# relocker_schematic_cleaned.net
KiCad netlist of a schematic drawn in EAGLE
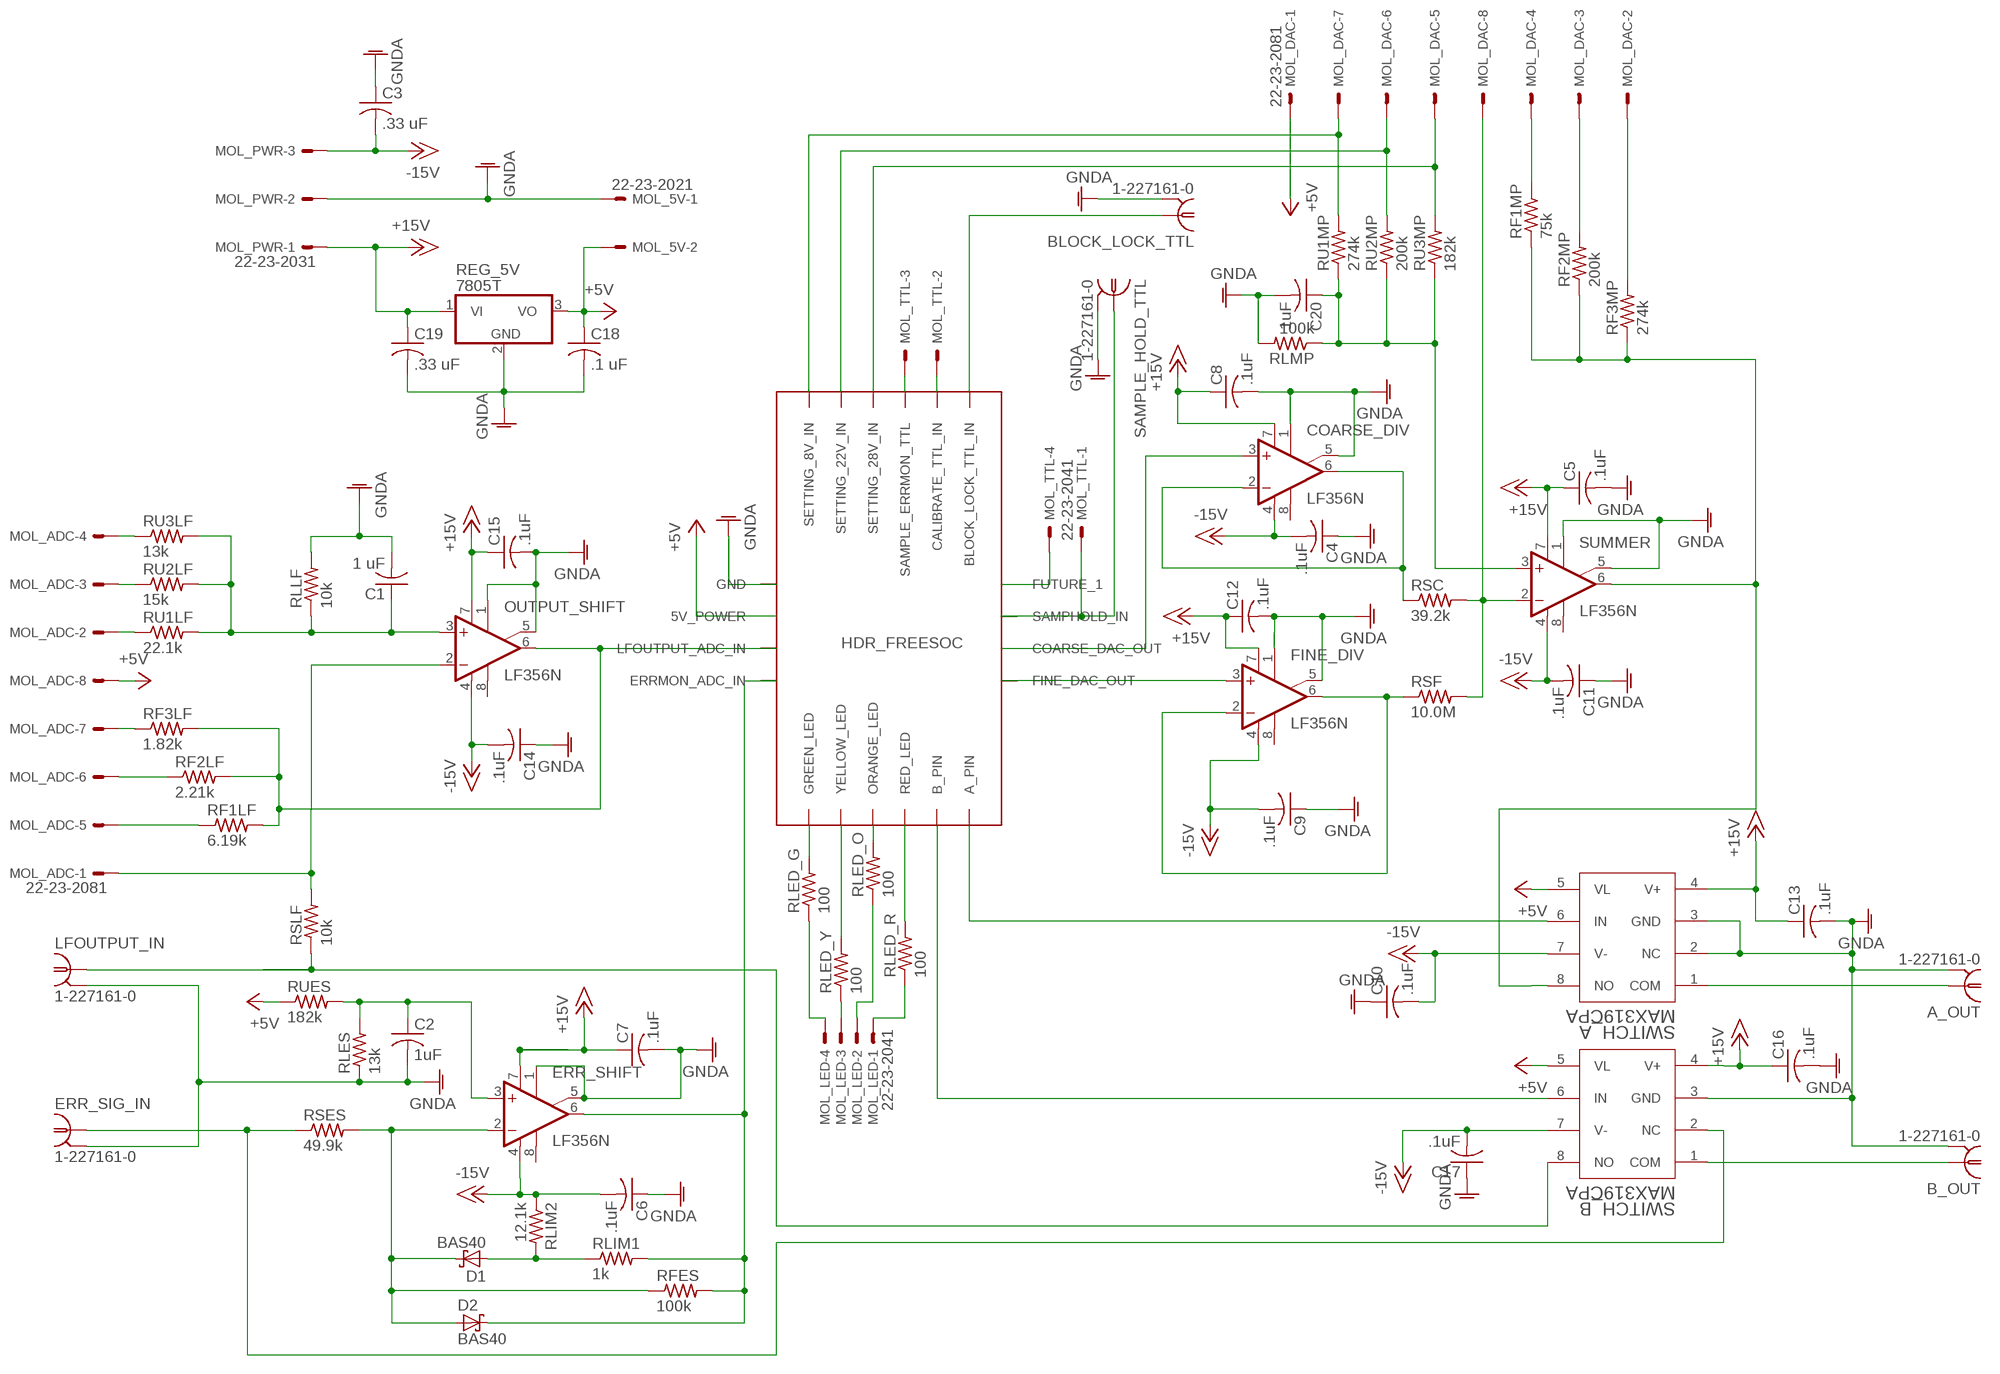
[diagram p0: schematic, sheet 1]

(export (version "E")
  (design (tool "Eeschema 10.0.6"))
  (components
    (comp (ref "A_OUT")
      (value "1-227161-0")
      (footprint "eagle-import:AMP_227161")
      (fields (field (name "MF") "TYCO ELECTRONICS") (field (name "MPN") "1-227161"))
      (libsource (lib "eagle-import") (part "?2271611--0"))
    )
    (comp (ref "BLOCK_LOCK_TTL")
      (value "1-227161-0")
      (footprint "eagle-import:AMP_227161")
      (fields (field (name "MF") "TYCO ELECTRONICS") (field (name "MPN") "1-227161"))
      (libsource (lib "eagle-import") (part "?2271611--0"))
    )
    (comp (ref "B_OUT")
      (value "1-227161-0")
      (footprint "eagle-import:AMP_227161")
      (fields (field (name "MF") "TYCO ELECTRONICS") (field (name "MPN") "1-227161"))
      (libsource (lib "eagle-import") (part "?2271611--0"))
    )
    (comp (ref "C1")
      (value "1 uF")
      (footprint "eagle-import:C0805")
      (libsource (lib "eagle-import") (part "C-USC0805"))
    )
    (comp (ref "C2")
      (value "1uF")
      (footprint "eagle-import:C0805")
      (libsource (lib "eagle-import") (part "C-USC0805"))
    )
    (comp (ref "C3")
      (value ".33 uF")
      (footprint "eagle-import:C0805")
      (libsource (lib "eagle-import") (part "C-USC0805"))
    )
    (comp (ref "C4")
      (value ".1uF")
      (footprint "eagle-import:C0805")
      (libsource (lib "eagle-import") (part "C-USC0805"))
    )
    (comp (ref "C5")
      (value ".1uF")
      (footprint "eagle-import:C0805")
      (libsource (lib "eagle-import") (part "C-USC0805"))
    )
    (comp (ref "C6")
      (value ".1uF")
      (footprint "eagle-import:C0805")
      (libsource (lib "eagle-import") (part "C-USC0805"))
    )
    (comp (ref "C7")
      (value ".1uF")
      (footprint "eagle-import:C0805")
      (libsource (lib "eagle-import") (part "C-USC0805"))
    )
    (comp (ref "C8")
      (value ".1uF")
      (footprint "eagle-import:C0805")
      (libsource (lib "eagle-import") (part "C-USC0805"))
    )
    (comp (ref "C9")
      (value ".1uF")
      (footprint "eagle-import:C0805")
      (libsource (lib "eagle-import") (part "C-USC0805"))
    )
    (comp (ref "C10")
      (value ".1uF")
      (footprint "eagle-import:C0805")
      (libsource (lib "eagle-import") (part "C-USC0805"))
    )
    (comp (ref "C11")
      (value ".1uF")
      (footprint "eagle-import:C0805")
      (libsource (lib "eagle-import") (part "C-USC0805"))
    )
    (comp (ref "C12")
      (value ".1uF")
      (footprint "eagle-import:C0805")
      (libsource (lib "eagle-import") (part "C-USC0805"))
    )
    (comp (ref "C13")
      (value ".1uF")
      (footprint "eagle-import:C0805")
      (libsource (lib "eagle-import") (part "C-USC0805"))
    )
    (comp (ref "C14")
      (value ".1uF")
      (footprint "eagle-import:C0805")
      (libsource (lib "eagle-import") (part "C-USC0805"))
    )
    (comp (ref "C15")
      (value ".1uF")
      (footprint "eagle-import:C0805")
      (libsource (lib "eagle-import") (part "C-USC0805"))
    )
    (comp (ref "C16")
      (value ".1uF")
      (footprint "eagle-import:C0805")
      (libsource (lib "eagle-import") (part "C-USC0805"))
    )
    (comp (ref "C17")
      (value ".1uF")
      (footprint "eagle-import:C0805")
      (libsource (lib "eagle-import") (part "C-USC0805"))
    )
    (comp (ref "C18")
      (value ".1 uF")
      (footprint "eagle-import:C0805")
      (libsource (lib "eagle-import") (part "C-USC0805"))
    )
    (comp (ref "C19")
      (value ".33 uF")
      (footprint "eagle-import:C0805")
      (libsource (lib "eagle-import") (part "C-USC0805"))
    )
    (comp (ref "C20")
      (value "1uF")
      (footprint "eagle-import:C0805")
      (libsource (lib "eagle-import") (part "C-USC0805"))
    )
    (comp (ref "COARSE_DIV")
      (value "LF356N")
      (footprint "eagle-import:DIL08")
      (libsource (lib "eagle-import") (part "LF356N"))
    )
    (comp (ref "D1")
      (value "BAS40")
      (footprint "eagle-import:SOT23")
      (libsource (lib "eagle-import") (part "BAS40"))
    )
    (comp (ref "D2")
      (value "BAS40")
      (footprint "eagle-import:SOT23")
      (libsource (lib "eagle-import") (part "BAS40"))
    )
    (comp (ref "ERR_SHIFT")
      (value "LF356N")
      (footprint "eagle-import:DIL08")
      (libsource (lib "eagle-import") (part "LF356N"))
    )
    (comp (ref "ERR_SIG_IN")
      (value "1-227161-0")
      (footprint "eagle-import:AMP_227161")
      (fields (field (name "MF") "TYCO ELECTRONICS") (field (name "MPN") "1-227161"))
      (libsource (lib "eagle-import") (part "?2271611--0"))
    )
    (comp (ref "FINE_DIV")
      (value "LF356N")
      (footprint "eagle-import:DIL08")
      (libsource (lib "eagle-import") (part "LF356N"))
    )
    (comp (ref "HDR_FREESOC")
      (value "FREESOC2_BREAKOUT")
      (footprint "eagle-import:FREESOC2_BREAKOUT")
      (libsource (lib "eagle-import") (part "FREESOC2_BREAKOUT"))
    )
    (comp (ref "LFOUTPUT_IN")
      (value "1-227161-0")
      (footprint "eagle-import:AMP_227161")
      (fields (field (name "MF") "TYCO ELECTRONICS") (field (name "MPN") "1-227161"))
      (libsource (lib "eagle-import") (part "?2271611--0"))
    )
    (comp (ref "MOL_5V")
      (value "22-23-2021")
      (footprint "eagle-import:22-23-2021")
      (fields (field (name "MF") "MOLEX"))
      (libsource (lib "eagle-import") (part "22-23-2021"))
    )
    (comp (ref "MOL_ADC")
      (value "22-23-2081")
      (footprint "eagle-import:22-23-2081")
      (fields (field (name "MF") "MOLEX"))
      (libsource (lib "eagle-import") (part "22-23-2081"))
    )
    (comp (ref "MOL_DAC")
      (value "22-23-2081")
      (footprint "eagle-import:22-23-2081")
      (fields (field (name "MF") "MOLEX"))
      (libsource (lib "eagle-import") (part "22-23-2081"))
    )
    (comp (ref "MOL_LED")
      (value "22-23-2041")
      (footprint "eagle-import:22-23-2041")
      (fields (field (name "MF") "MOLEX"))
      (libsource (lib "eagle-import") (part "22-23-2041"))
    )
    (comp (ref "MOL_PWR")
      (value "22-23-2031")
      (footprint "eagle-import:22-23-2031")
      (fields (field (name "MF") "MOLEX"))
      (libsource (lib "eagle-import") (part "22-23-2031"))
    )
    (comp (ref "MOL_TTL")
      (value "22-23-2041")
      (footprint "eagle-import:22-23-2041")
      (fields (field (name "MF") "MOLEX"))
      (libsource (lib "eagle-import") (part "22-23-2041"))
    )
    (comp (ref "OUTPUT_SHIFT")
      (value "LF356N")
      (footprint "eagle-import:DIL08")
      (libsource (lib "eagle-import") (part "LF356N"))
    )
    (comp (ref "REG_5V")
      (value "7805T")
      (footprint "eagle-import:TO220H")
      (libsource (lib "eagle-import") (part "78T05"))
    )
    (comp (ref "RF1LF")
      (value "6.19k")
      (footprint "eagle-import:R0805")
      (libsource (lib "eagle-import") (part "R-US_R0805"))
    )
    (comp (ref "RF1MP")
      (value "75k")
      (footprint "eagle-import:R0805")
      (libsource (lib "eagle-import") (part "R-US_R0805"))
    )
    (comp (ref "RF2LF")
      (value "2.21k")
      (footprint "eagle-import:R0805")
      (libsource (lib "eagle-import") (part "R-US_R0805"))
    )
    (comp (ref "RF2MP")
      (value "200k")
      (footprint "eagle-import:R0805")
      (libsource (lib "eagle-import") (part "R-US_R0805"))
    )
    (comp (ref "RF3LF")
      (value "1.82k")
      (footprint "eagle-import:R0805")
      (libsource (lib "eagle-import") (part "R-US_R0805"))
    )
    (comp (ref "RF3MP")
      (value "274k")
      (footprint "eagle-import:R0805")
      (libsource (lib "eagle-import") (part "R-US_R0805"))
    )
    (comp (ref "RFES")
      (value "100k")
      (footprint "eagle-import:R0805")
      (libsource (lib "eagle-import") (part "R-US_R0805"))
    )
    (comp (ref "RLED_G")
      (value "100")
      (footprint "eagle-import:R0805")
      (libsource (lib "eagle-import") (part "R-US_R0805"))
    )
    (comp (ref "RLED_O")
      (value "100")
      (footprint "eagle-import:R0805")
      (libsource (lib "eagle-import") (part "R-US_R0805"))
    )
    (comp (ref "RLED_R")
      (value "100")
      (footprint "eagle-import:R0805")
      (libsource (lib "eagle-import") (part "R-US_R0805"))
    )
    (comp (ref "RLED_Y")
      (value "100")
      (footprint "eagle-import:R0805")
      (libsource (lib "eagle-import") (part "R-US_R0805"))
    )
    (comp (ref "RLES")
      (value "13k")
      (footprint "eagle-import:R0805")
      (libsource (lib "eagle-import") (part "R-US_R0805"))
    )
    (comp (ref "RLIM1")
      (value "1k")
      (footprint "eagle-import:R0805")
      (libsource (lib "eagle-import") (part "R-US_R0805"))
    )
    (comp (ref "RLIM2")
      (value "12.1k")
      (footprint "eagle-import:R0805")
      (libsource (lib "eagle-import") (part "R-US_R0805"))
    )
    (comp (ref "RLLF")
      (value "10k")
      (footprint "eagle-import:R0805")
      (libsource (lib "eagle-import") (part "R-US_R0805"))
    )
    (comp (ref "RLMP")
      (value "100k")
      (footprint "eagle-import:R0805")
      (libsource (lib "eagle-import") (part "R-US_R0805"))
    )
    (comp (ref "RSC")
      (value "39.2k")
      (footprint "eagle-import:R0805")
      (libsource (lib "eagle-import") (part "R-US_R0805"))
    )
    (comp (ref "RSES")
      (value "49.9k")
      (footprint "eagle-import:R0805")
      (libsource (lib "eagle-import") (part "R-US_R0805"))
    )
    (comp (ref "RSF")
      (value "10.0M")
      (footprint "eagle-import:R0805")
      (libsource (lib "eagle-import") (part "R-US_R0805"))
    )
    (comp (ref "RSLF")
      (value "10k")
      (footprint "eagle-import:R0805")
      (libsource (lib "eagle-import") (part "R-US_R0805"))
    )
    (comp (ref "RU1LF")
      (value "22.1k")
      (footprint "eagle-import:R0805")
      (libsource (lib "eagle-import") (part "R-US_R0805"))
    )
    (comp (ref "RU1MP")
      (value "274k")
      (footprint "eagle-import:R0805")
      (libsource (lib "eagle-import") (part "R-US_R0805"))
    )
    (comp (ref "RU2LF")
      (value "15k")
      (footprint "eagle-import:R0805")
      (libsource (lib "eagle-import") (part "R-US_R0805"))
    )
    (comp (ref "RU2MP")
      (value "200k")
      (footprint "eagle-import:R0805")
      (libsource (lib "eagle-import") (part "R-US_R0805"))
    )
    (comp (ref "RU3LF")
      (value "13k")
      (footprint "eagle-import:R0805")
      (libsource (lib "eagle-import") (part "R-US_R0805"))
    )
    (comp (ref "RU3MP")
      (value "182k")
      (footprint "eagle-import:R0805")
      (libsource (lib "eagle-import") (part "R-US_R0805"))
    )
    (comp (ref "RUES")
      (value "182k")
      (footprint "eagle-import:R0805")
      (libsource (lib "eagle-import") (part "R-US_R0805"))
    )
    (comp (ref "SAMPLE_HOLD_TTL")
      (value "1-227161-0")
      (footprint "eagle-import:AMP_227161")
      (fields (field (name "MF") "TYCO ELECTRONICS") (field (name "MPN") "1-227161"))
      (libsource (lib "eagle-import") (part "?2271611--0"))
    )
    (comp (ref "SUMMER")
      (value "LF356N")
      (footprint "eagle-import:DIL08")
      (libsource (lib "eagle-import") (part "LF356N"))
    )
    (comp (ref "SWITCH_A")
      (value "MAX319CPA")
      (footprint "eagle-import:21-0043D_8")
      (libsource (lib "eagle-import") (part "MAX319CPA"))
    )
    (comp (ref "SWITCH_B")
      (value "MAX319CPA")
      (footprint "eagle-import:21-0043D_8")
      (libsource (lib "eagle-import") (part "MAX319CPA"))
    )
  )
  (nets
    (net (code "1") (name "+5V") (class "Default")
      (node (ref "C18") (pin "1") (pinfunction "1_1") (pintype "passive"))
      (node (ref "HDR_FREESOC") (pin "1") (pinfunction "5V_POWER_1") (pintype "input"))
      (node (ref "MOL_5V") (pin "2") (pinfunction "S_2") (pintype "passive"))
      (node (ref "MOL_ADC") (pin "8") (pinfunction "S_8") (pintype "passive"))
      (node (ref "MOL_DAC") (pin "1") (pinfunction "S_1") (pintype "passive"))
      (node (ref "REG_5V") (pin "3") (pinfunction "VO_3") (pintype "passive"))
      (node (ref "RUES") (pin "1") (pinfunction "1_1") (pintype "passive"))
      (node (ref "SWITCH_A") (pin "5") (pinfunction "VL_5") (pintype "power_in"))
      (node (ref "SWITCH_B") (pin "5") (pinfunction "VL_5") (pintype "power_in"))
    )
    (net (code "2") (name "+15V") (class "Default")
      (node (ref "C12") (pin "1") (pinfunction "1_1") (pintype "passive"))
      (node (ref "C13") (pin "1") (pinfunction "1_1") (pintype "passive"))
      (node (ref "C15") (pin "1") (pinfunction "1_1") (pintype "passive"))
      (node (ref "C16") (pin "1") (pinfunction "1_1") (pintype "passive"))
      (node (ref "C19") (pin "1") (pinfunction "1_1") (pintype "passive"))
      (node (ref "C5") (pin "1") (pinfunction "1_1") (pintype "passive"))
      (node (ref "C7") (pin "1") (pinfunction "1_1") (pintype "passive"))
      (node (ref "C8") (pin "1") (pinfunction "1_1") (pintype "passive"))
      (node (ref "COARSE_DIV") (pin "7") (pinfunction "V+_7") (pintype "power_in"))
      (node (ref "ERR_SHIFT") (pin "7") (pinfunction "V+_7") (pintype "power_in"))
      (node (ref "FINE_DIV") (pin "7") (pinfunction "V+_7") (pintype "power_in"))
      (node (ref "MOL_PWR") (pin "1") (pinfunction "S_1") (pintype "passive"))
      (node (ref "OUTPUT_SHIFT") (pin "7") (pinfunction "V+_7") (pintype "power_in"))
      (node (ref "REG_5V") (pin "1") (pinfunction "VI_1") (pintype "input"))
      (node (ref "SUMMER") (pin "7") (pinfunction "V+_7") (pintype "power_in"))
      (node (ref "SWITCH_A") (pin "4") (pinfunction "V+_4") (pintype "power_in"))
      (node (ref "SWITCH_B") (pin "4") (pinfunction "V+_4") (pintype "power_in"))
    )
    (net (code "3") (name "-15V") (class "Default")
      (node (ref "C10") (pin "2") (pinfunction "2_2") (pintype "passive"))
      (node (ref "C11") (pin "2") (pinfunction "2_2") (pintype "passive"))
      (node (ref "C14") (pin "2") (pinfunction "2_2") (pintype "passive"))
      (node (ref "C17") (pin "2") (pinfunction "2_2") (pintype "passive"))
      (node (ref "C3") (pin "2") (pinfunction "2_2") (pintype "passive"))
      (node (ref "C4") (pin "2") (pinfunction "2_2") (pintype "passive"))
      (node (ref "C6") (pin "2") (pinfunction "2_2") (pintype "passive"))
      (node (ref "C9") (pin "2") (pinfunction "2_2") (pintype "passive"))
      (node (ref "COARSE_DIV") (pin "4") (pinfunction "V-_4") (pintype "power_in"))
      (node (ref "ERR_SHIFT") (pin "4") (pinfunction "V-_4") (pintype "power_in"))
      (node (ref "FINE_DIV") (pin "4") (pinfunction "V-_4") (pintype "power_in"))
      (node (ref "MOL_PWR") (pin "3") (pinfunction "S_3") (pintype "passive"))
      (node (ref "OUTPUT_SHIFT") (pin "4") (pinfunction "V-_4") (pintype "power_in"))
      (node (ref "RLIM2") (pin "1") (pinfunction "1_1") (pintype "passive"))
      (node (ref "SUMMER") (pin "4") (pinfunction "V-_4") (pintype "power_in"))
      (node (ref "SWITCH_A") (pin "7") (pinfunction "V-_7") (pintype "power_in"))
      (node (ref "SWITCH_B") (pin "7") (pinfunction "V-_7") (pintype "power_in"))
    )
    (net (code "4") (name "GNDA") (class "Default")
      (node (ref "A_OUT") (pin "2") (pinfunction "2_2") (pintype "passive"))
      (node (ref "BLOCK_LOCK_TTL") (pin "2") (pinfunction "2_2") (pintype "passive"))
      (node (ref "B_OUT") (pin "2") (pinfunction "2_2") (pintype "passive"))
      (node (ref "C1") (pin "2") (pinfunction "2_2") (pintype "passive"))
      (node (ref "C10") (pin "1") (pinfunction "1_1") (pintype "passive"))
      (node (ref "C11") (pin "1") (pinfunction "1_1") (pintype "passive"))
      (node (ref "C12") (pin "2") (pinfunction "2_2") (pintype "passive"))
      (node (ref "C13") (pin "2") (pinfunction "2_2") (pintype "passive"))
      (node (ref "C14") (pin "1") (pinfunction "1_1") (pintype "passive"))
      (node (ref "C15") (pin "2") (pinfunction "2_2") (pintype "passive"))
      (node (ref "C16") (pin "2") (pinfunction "2_2") (pintype "passive"))
      (node (ref "C17") (pin "1") (pinfunction "1_1") (pintype "passive"))
      (node (ref "C18") (pin "2") (pinfunction "2_2") (pintype "passive"))
      (node (ref "C19") (pin "2") (pinfunction "2_2") (pintype "passive"))
      (node (ref "C2") (pin "2") (pinfunction "2_2") (pintype "passive"))
      (node (ref "C20") (pin "2") (pinfunction "2_2") (pintype "passive"))
      (node (ref "C3") (pin "1") (pinfunction "1_1") (pintype "passive"))
      (node (ref "C4") (pin "1") (pinfunction "1_1") (pintype "passive"))
      (node (ref "C5") (pin "2") (pinfunction "2_2") (pintype "passive"))
      (node (ref "C6") (pin "1") (pinfunction "1_1") (pintype "passive"))
      (node (ref "C7") (pin "2") (pinfunction "2_2") (pintype "passive"))
      (node (ref "C8") (pin "2") (pinfunction "2_2") (pintype "passive"))
      (node (ref "C9") (pin "1") (pinfunction "1_1") (pintype "passive"))
      (node (ref "COARSE_DIV") (pin "1") (pinfunction "ON1_1") (pintype "passive"))
      (node (ref "COARSE_DIV") (pin "5") (pinfunction "ON2_5") (pintype "passive"))
      (node (ref "ERR_SHIFT") (pin "1") (pinfunction "ON1_1") (pintype "passive"))
      (node (ref "ERR_SHIFT") (pin "5") (pinfunction "ON2_5") (pintype "passive"))
      (node (ref "ERR_SIG_IN") (pin "2") (pinfunction "2_2") (pintype "passive"))
      (node (ref "FINE_DIV") (pin "1") (pinfunction "ON1_1") (pintype "passive"))
      (node (ref "FINE_DIV") (pin "5") (pinfunction "ON2_5") (pintype "passive"))
      (node (ref "HDR_FREESOC") (pin "2") (pinfunction "GND_2") (pintype "input"))
      (node (ref "LFOUTPUT_IN") (pin "2") (pinfunction "2_2") (pintype "passive"))
      (node (ref "MOL_5V") (pin "1") (pinfunction "S_1") (pintype "passive"))
      (node (ref "MOL_PWR") (pin "2") (pinfunction "S_2") (pintype "passive"))
      (node (ref "OUTPUT_SHIFT") (pin "1") (pinfunction "ON1_1") (pintype "passive"))
      (node (ref "OUTPUT_SHIFT") (pin "5") (pinfunction "ON2_5") (pintype "passive"))
      (node (ref "REG_5V") (pin "2") (pinfunction "GND_2") (pintype "passive"))
      (node (ref "RLES") (pin "1") (pinfunction "1_1") (pintype "passive"))
      (node (ref "RLLF") (pin "2") (pinfunction "2_2") (pintype "passive"))
      (node (ref "RLMP") (pin "2") (pinfunction "2_2") (pintype "passive"))
      (node (ref "SAMPLE_HOLD_TTL") (pin "2") (pinfunction "2_2") (pintype "passive"))
      (node (ref "SUMMER") (pin "1") (pinfunction "ON1_1") (pintype "passive"))
      (node (ref "SUMMER") (pin "5") (pinfunction "ON2_5") (pintype "passive"))
      (node (ref "SWITCH_A") (pin "2") (pinfunction "NC_2") (pintype "passive"))
      (node (ref "SWITCH_A") (pin "3") (pinfunction "GND_3") (pintype "power_in"))
      (node (ref "SWITCH_B") (pin "3") (pinfunction "GND_3") (pintype "power_in"))
    )
    (net (code "5") (name "Net-(COARSE_DIV-+IN)") (class "Default")
      (node (ref "COARSE_DIV") (pin "3") (pinfunction "+IN_3") (pintype "input"))
      (node (ref "HDR_FREESOC") (pin "10") (pinfunction "COARSE_DAC_OUT_10") (pintype "bidirectional"))
    )
    (net (code "6") (name "Net-(COARSE_DIV--IN)") (class "Default")
      (node (ref "COARSE_DIV") (pin "2") (pinfunction "-IN_2") (pintype "input"))
      (node (ref "COARSE_DIV") (pin "6") (pinfunction "OUT_6") (pintype "output"))
      (node (ref "RSC") (pin "1") (pinfunction "1_1") (pintype "passive"))
    )
    (net (code "7") (name "Net-(D1-A)") (class "Default")
      (node (ref "D1") (pin "1") (pinfunction "A_1") (pintype "passive"))
      (node (ref "RLIM1") (pin "1") (pinfunction "1_1") (pintype "passive"))
      (node (ref "RLIM2") (pin "2") (pinfunction "2_2") (pintype "passive"))
    )
    (net (code "8") (name "Net-(D1-C)") (class "Default")
      (node (ref "D1") (pin "3") (pinfunction "C_3") (pintype "passive"))
      (node (ref "D2") (pin "1") (pinfunction "A_1") (pintype "passive"))
      (node (ref "ERR_SHIFT") (pin "2") (pinfunction "-IN_2") (pintype "input"))
      (node (ref "RFES") (pin "1") (pinfunction "1_1") (pintype "passive"))
      (node (ref "RSES") (pin "2") (pinfunction "2_2") (pintype "passive"))
    )
    (net (code "9") (name "Net-(D2-C)") (class "Default")
      (node (ref "D2") (pin "3") (pinfunction "C_3") (pintype "passive"))
      (node (ref "ERR_SHIFT") (pin "6") (pinfunction "OUT_6") (pintype "output"))
      (node (ref "HDR_FREESOC") (pin "4") (pinfunction "ERRMON_ADC_IN_4") (pintype "input"))
      (node (ref "RFES") (pin "2") (pinfunction "2_2") (pintype "passive"))
      (node (ref "RLIM1") (pin "2") (pinfunction "2_2") (pintype "passive"))
    )
    (net (code "10") (name "Net-(ERR_SHIFT-+IN)") (class "Default")
      (node (ref "C2") (pin "1") (pinfunction "1_1") (pintype "passive"))
      (node (ref "ERR_SHIFT") (pin "3") (pinfunction "+IN_3") (pintype "input"))
      (node (ref "RLES") (pin "2") (pinfunction "2_2") (pintype "passive"))
      (node (ref "RUES") (pin "2") (pinfunction "2_2") (pintype "passive"))
    )
    (net (code "11") (name "Net-(FINE_DIV-+IN)") (class "Default")
      (node (ref "FINE_DIV") (pin "3") (pinfunction "+IN_3") (pintype "input"))
      (node (ref "HDR_FREESOC") (pin "11") (pinfunction "FINE_DAC_OUT_11") (pintype "bidirectional"))
    )
    (net (code "12") (name "Net-(FINE_DIV--IN)") (class "Default")
      (node (ref "FINE_DIV") (pin "2") (pinfunction "-IN_2") (pintype "input"))
      (node (ref "FINE_DIV") (pin "6") (pinfunction "OUT_6") (pintype "output"))
      (node (ref "RSF") (pin "1") (pinfunction "1_1") (pintype "passive"))
    )
    (net (code "13") (name "Net-(HDR_FREESOC-A_PIN)") (class "Default")
      (node (ref "HDR_FREESOC") (pin "6") (pinfunction "A_PIN_6") (pintype "bidirectional"))
      (node (ref "SWITCH_A") (pin "6") (pinfunction "IN_6") (pintype "input"))
    )
    (net (code "14") (name "Net-(HDR_FREESOC-BLOCK_LOCK_TTL_IN)") (class "Default")
      (node (ref "BLOCK_LOCK_TTL") (pin "1") (pinfunction "1_1") (pintype "passive"))
      (node (ref "HDR_FREESOC") (pin "12") (pinfunction "BLOCK_LOCK_TTL_IN_12") (pintype "bidirectional"))
    )
    (net (code "15") (name "Net-(HDR_FREESOC-B_PIN)") (class "Default")
      (node (ref "HDR_FREESOC") (pin "5") (pinfunction "B_PIN_5") (pintype "bidirectional"))
      (node (ref "SWITCH_B") (pin "6") (pinfunction "IN_6") (pintype "input"))
    )
    (net (code "16") (name "Net-(HDR_FREESOC-CALIBRATE_TTL_IN)") (class "Default")
      (node (ref "HDR_FREESOC") (pin "14") (pinfunction "CALIBRATE_TTL_IN_14") (pintype "bidirectional"))
      (node (ref "MOL_TTL") (pin "2") (pinfunction "S_2") (pintype "passive"))
    )
    (net (code "17") (name "Net-(HDR_FREESOC-FUTURE_1)") (class "Default")
      (node (ref "HDR_FREESOC") (pin "16") (pinfunction "FUTURE_1_16") (pintype "bidirectional"))
      (node (ref "MOL_TTL") (pin "4") (pinfunction "S_4") (pintype "passive"))
    )
    (net (code "18") (name "Net-(HDR_FREESOC-GREEN_LED)") (class "Default")
      (node (ref "HDR_FREESOC") (pin "20") (pinfunction "GREEN_LED_20") (pintype "bidirectional"))
      (node (ref "RLED_G") (pin "2") (pinfunction "2_2") (pintype "passive"))
    )
    (net (code "19") (name "Net-(HDR_FREESOC-LFOUTPUT_ADC_IN)") (class "Default")
      (node (ref "HDR_FREESOC") (pin "3") (pinfunction "LFOUTPUT_ADC_IN_3") (pintype "input"))
      (node (ref "OUTPUT_SHIFT") (pin "6") (pinfunction "OUT_6") (pintype "output"))
      (node (ref "RF1LF") (pin "2") (pinfunction "2_2") (pintype "passive"))
      (node (ref "RF2LF") (pin "2") (pinfunction "2_2") (pintype "passive"))
      (node (ref "RF3LF") (pin "2") (pinfunction "2_2") (pintype "passive"))
    )
    (net (code "20") (name "Net-(HDR_FREESOC-ORANGE_LED)") (class "Default")
      (node (ref "HDR_FREESOC") (pin "18") (pinfunction "ORANGE_LED_18") (pintype "bidirectional"))
      (node (ref "RLED_O") (pin "2") (pinfunction "2_2") (pintype "passive"))
    )
    (net (code "21") (name "Net-(HDR_FREESOC-RED_LED)") (class "Default")
      (node (ref "HDR_FREESOC") (pin "17") (pinfunction "RED_LED_17") (pintype "bidirectional"))
      (node (ref "RLED_R") (pin "2") (pinfunction "2_2") (pintype "passive"))
    )
    (net (code "22") (name "Net-(HDR_FREESOC-SAMPHOLD_IN)") (class "Default")
      (node (ref "HDR_FREESOC") (pin "13") (pinfunction "SAMPHOLD_IN_13") (pintype "bidirectional"))
      (node (ref "MOL_TTL") (pin "1") (pinfunction "S_1") (pintype "passive"))
      (node (ref "SAMPLE_HOLD_TTL") (pin "1") (pinfunction "1_1") (pintype "passive"))
    )
    (net (code "23") (name "Net-(HDR_FREESOC-SAMPLE_ERRMON_TTL)") (class "Default")
      (node (ref "HDR_FREESOC") (pin "15") (pinfunction "SAMPLE_ERRMON_TTL_15") (pintype "bidirectional"))
      (node (ref "MOL_TTL") (pin "3") (pinfunction "S_3") (pintype "passive"))
    )
    (net (code "24") (name "Net-(HDR_FREESOC-SETTING_8V_IN)") (class "Default")
      (node (ref "HDR_FREESOC") (pin "9") (pinfunction "SETTING_8V_IN_9") (pintype "bidirectional"))
      (node (ref "MOL_DAC") (pin "7") (pinfunction "S_7") (pintype "passive"))
      (node (ref "RU1MP") (pin "2") (pinfunction "2_2") (pintype "passive"))
    )
    (net (code "25") (name "Net-(HDR_FREESOC-SETTING_22V_IN)") (class "Default")
      (node (ref "HDR_FREESOC") (pin "8") (pinfunction "SETTING_22V_IN_8") (pintype "bidirectional"))
      (node (ref "MOL_DAC") (pin "6") (pinfunction "S_6") (pintype "passive"))
      (node (ref "RU2MP") (pin "2") (pinfunction "2_2") (pintype "passive"))
    )
    (net (code "26") (name "Net-(HDR_FREESOC-SETTING_28V_IN)") (class "Default")
      (node (ref "HDR_FREESOC") (pin "7") (pinfunction "SETTING_28V_IN_7") (pintype "bidirectional"))
      (node (ref "MOL_DAC") (pin "5") (pinfunction "S_5") (pintype "passive"))
      (node (ref "RU3MP") (pin "2") (pinfunction "2_2") (pintype "passive"))
    )
    (net (code "27") (name "Net-(HDR_FREESOC-YELLOW_LED)") (class "Default")
      (node (ref "HDR_FREESOC") (pin "19") (pinfunction "YELLOW_LED_19") (pintype "bidirectional"))
      (node (ref "RLED_Y") (pin "2") (pinfunction "2_2") (pintype "passive"))
    )
    (net (code "28") (name "Net-(MOL_ADCA-S)") (class "Default")
      (node (ref "MOL_ADC") (pin "1") (pinfunction "S_1") (pintype "passive"))
      (node (ref "OUTPUT_SHIFT") (pin "2") (pinfunction "-IN_2") (pintype "input"))
      (node (ref "RSLF") (pin "2") (pinfunction "2_2") (pintype "passive"))
    )
    (net (code "29") (name "Net-(MOL_ADCB-S)") (class "Default")
      (node (ref "MOL_ADC") (pin "2") (pinfunction "S_2") (pintype "passive"))
      (node (ref "RU1LF") (pin "1") (pinfunction "1_1") (pintype "passive"))
    )
    (net (code "30") (name "Net-(MOL_ADCC-S)") (class "Default")
      (node (ref "MOL_ADC") (pin "3") (pinfunction "S_3") (pintype "passive"))
      (node (ref "RU2LF") (pin "1") (pinfunction "1_1") (pintype "passive"))
    )
    (net (code "31") (name "Net-(MOL_ADCD-S)") (class "Default")
      (node (ref "MOL_ADC") (pin "4") (pinfunction "S_4") (pintype "passive"))
      (node (ref "RU3LF") (pin "1") (pinfunction "1_1") (pintype "passive"))
    )
    (net (code "32") (name "Net-(MOL_ADCE-S)") (class "Default")
      (node (ref "MOL_ADC") (pin "5") (pinfunction "S_5") (pintype "passive"))
      (node (ref "RF1LF") (pin "1") (pinfunction "1_1") (pintype "passive"))
    )
    (net (code "33") (name "Net-(MOL_ADCF-S)") (class "Default")
      (node (ref "MOL_ADC") (pin "6") (pinfunction "S_6") (pintype "passive"))
      (node (ref "RF2LF") (pin "1") (pinfunction "1_1") (pintype "passive"))
    )
    (net (code "34") (name "Net-(MOL_ADCG-S)") (class "Default")
      (node (ref "MOL_ADC") (pin "7") (pinfunction "S_7") (pintype "passive"))
      (node (ref "RF3LF") (pin "1") (pinfunction "1_1") (pintype "passive"))
    )
    (net (code "35") (name "Net-(MOL_DACB-S)") (class "Default")
      (node (ref "MOL_DAC") (pin "2") (pinfunction "S_2") (pintype "passive"))
      (node (ref "RF3MP") (pin "2") (pinfunction "2_2") (pintype "passive"))
    )
    (net (code "36") (name "Net-(MOL_DACC-S)") (class "Default")
      (node (ref "MOL_DAC") (pin "3") (pinfunction "S_3") (pintype "passive"))
      (node (ref "RF2MP") (pin "2") (pinfunction "2_2") (pintype "passive"))
    )
    (net (code "37") (name "Net-(MOL_DACD-S)") (class "Default")
      (node (ref "MOL_DAC") (pin "4") (pinfunction "S_4") (pintype "passive"))
      (node (ref "RF1MP") (pin "2") (pinfunction "2_2") (pintype "passive"))
    )
    (net (code "38") (name "Net-(MOL_DACH-S)") (class "Default")
      (node (ref "MOL_DAC") (pin "8") (pinfunction "S_8") (pintype "passive"))
      (node (ref "RSC") (pin "2") (pinfunction "2_2") (pintype "passive"))
      (node (ref "RSF") (pin "2") (pinfunction "2_2") (pintype "passive"))
      (node (ref "SUMMER") (pin "2") (pinfunction "-IN_2") (pintype "input"))
    )
    (net (code "39") (name "Net-(MOL_LEDA-S)") (class "Default")
      (node (ref "MOL_LED") (pin "1") (pinfunction "S_1") (pintype "passive"))
      (node (ref "RLED_R") (pin "1") (pinfunction "1_1") (pintype "passive"))
    )
    (net (code "40") (name "Net-(MOL_LEDB-S)") (class "Default")
      (node (ref "MOL_LED") (pin "2") (pinfunction "S_2") (pintype "passive"))
      (node (ref "RLED_O") (pin "1") (pinfunction "1_1") (pintype "passive"))
    )
    (net (code "41") (name "Net-(MOL_LEDC-S)") (class "Default")
      (node (ref "MOL_LED") (pin "3") (pinfunction "S_3") (pintype "passive"))
      (node (ref "RLED_Y") (pin "1") (pinfunction "1_1") (pintype "passive"))
    )
    (net (code "42") (name "Net-(MOL_LEDD-S)") (class "Default")
      (node (ref "MOL_LED") (pin "4") (pinfunction "S_4") (pintype "passive"))
      (node (ref "RLED_G") (pin "1") (pinfunction "1_1") (pintype "passive"))
    )
    (net (code "43") (name "Net-(OUTPUT_SHIFT-+IN)") (class "Default")
      (node (ref "C1") (pin "1") (pinfunction "1_1") (pintype "passive"))
      (node (ref "OUTPUT_SHIFT") (pin "3") (pinfunction "+IN_3") (pintype "input"))
      (node (ref "RLLF") (pin "1") (pinfunction "1_1") (pintype "passive"))
      (node (ref "RU1LF") (pin "2") (pinfunction "2_2") (pintype "passive"))
      (node (ref "RU2LF") (pin "2") (pinfunction "2_2") (pintype "passive"))
      (node (ref "RU3LF") (pin "2") (pinfunction "2_2") (pintype "passive"))
    )
    (net (code "44") (name "Net-(SUMMER-+IN)") (class "Default")
      (node (ref "C20") (pin "1") (pinfunction "1_1") (pintype "passive"))
      (node (ref "RLMP") (pin "1") (pinfunction "1_1") (pintype "passive"))
      (node (ref "RU1MP") (pin "1") (pinfunction "1_1") (pintype "passive"))
      (node (ref "RU2MP") (pin "1") (pinfunction "1_1") (pintype "passive"))
      (node (ref "RU3MP") (pin "1") (pinfunction "1_1") (pintype "passive"))
      (node (ref "SUMMER") (pin "3") (pinfunction "+IN_3") (pintype "input"))
    )
    (net (code "45") (name "Net-(SUMMER-OUT)") (class "Default")
      (node (ref "RF1MP") (pin "1") (pinfunction "1_1") (pintype "passive"))
      (node (ref "RF2MP") (pin "1") (pinfunction "1_1") (pintype "passive"))
      (node (ref "RF3MP") (pin "1") (pinfunction "1_1") (pintype "passive"))
      (node (ref "SUMMER") (pin "6") (pinfunction "OUT_6") (pintype "output"))
      (node (ref "SWITCH_A") (pin "8") (pinfunction "NO_8") (pintype "bidirectional"))
    )
    (net (code "46") (name "Net-(SWITCH_A-COM)") (class "Default")
      (node (ref "A_OUT") (pin "1") (pinfunction "1_1") (pintype "passive"))
      (node (ref "SWITCH_A") (pin "1") (pinfunction "COM_1") (pintype "bidirectional"))
    )
    (net (code "47") (name "Net-(SWITCH_B-COM)") (class "Default")
      (node (ref "B_OUT") (pin "1") (pinfunction "1_1") (pintype "passive"))
      (node (ref "SWITCH_B") (pin "1") (pinfunction "COM_1") (pintype "bidirectional"))
    )
    (net (code "48") (name "Net-(SWITCH_B-NC)") (class "Default")
      (node (ref "ERR_SIG_IN") (pin "1") (pinfunction "1_1") (pintype "passive"))
      (node (ref "RSES") (pin "1") (pinfunction "1_1") (pintype "passive"))
      (node (ref "SWITCH_B") (pin "2") (pinfunction "NC_2") (pintype "passive"))
    )
    (net (code "49") (name "Net-(SWITCH_B-NO)") (class "Default")
      (node (ref "LFOUTPUT_IN") (pin "1") (pinfunction "1_1") (pintype "passive"))
      (node (ref "RSLF") (pin "1") (pinfunction "1_1") (pintype "passive"))
      (node (ref "SWITCH_B") (pin "8") (pinfunction "NO_8") (pintype "bidirectional"))
    )
    (net (code "50") (name "unconnected-(COARSE_DIV-OPT-Pad8)") (class "Default")
      (node (ref "COARSE_DIV") (pin "8") (pinfunction "OPT_8") (pintype "passive"))
    )
    (net (code "51") (name "unconnected-(ERR_SHIFT-OPT-Pad8)") (class "Default")
      (node (ref "ERR_SHIFT") (pin "8") (pinfunction "OPT_8") (pintype "passive"))
    )
    (net (code "52") (name "unconnected-(FINE_DIV-OPT-Pad8)") (class "Default")
      (node (ref "FINE_DIV") (pin "8") (pinfunction "OPT_8") (pintype "passive"))
    )
    (net (code "53") (name "unconnected-(OUTPUT_SHIFT-OPT-Pad8)") (class "Default")
      (node (ref "OUTPUT_SHIFT") (pin "8") (pinfunction "OPT_8") (pintype "passive"))
    )
    (net (code "54") (name "unconnected-(SUMMER-OPT-Pad8)") (class "Default")
      (node (ref "SUMMER") (pin "8") (pinfunction "OPT_8") (pintype "passive"))
    )
  )
)
